# Sheet1.net
KiCad netlist of a schematic drawn in Altium Designer
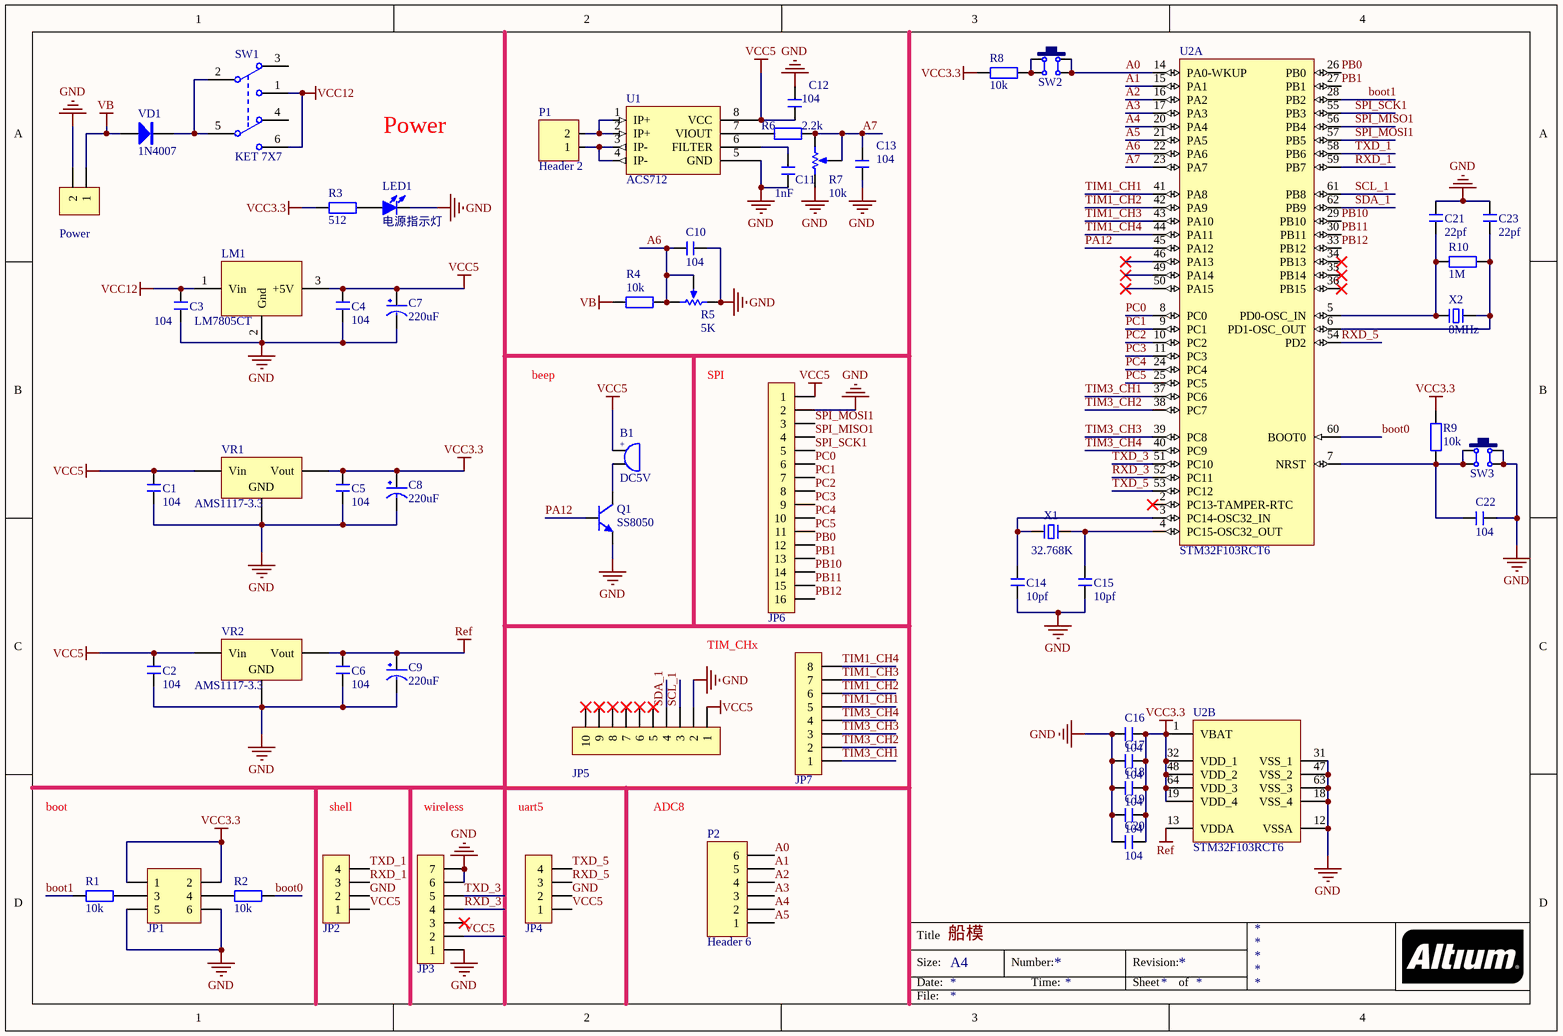
[diagram p0: Sheet1.SchDoc]

(export (version "E")
  (design (tool "Eeschema 10.0.6"))
  (components
    (comp (ref "B1")
      (value "DC5V")
      (footprint "蜂鸣器")
      (description "蜂鸣器")
      (fields (field (name "版权归属") "源创客"))
      (libsource (lib "未分类器件") (part "BEEP"))
    )
    (comp (ref "C1")
      (value "104")
      (footprint "0805")
      (description "无极性贴片电容")
      (fields (field (name "版权归属") "源创客"))
      (libsource (lib "电阻-电容-电感") (part "C"))
    )
    (comp (ref "C2")
      (value "104")
      (footprint "0805")
      (description "无极性贴片电容")
      (fields (field (name "版权归属") "源创客"))
      (libsource (lib "电阻-电容-电感") (part "C"))
    )
    (comp (ref "C3")
      (value "104")
      (footprint "0805")
      (description "无极性贴片电容")
      (fields (field (name "版权归属") "源创客"))
      (libsource (lib "电阻-电容-电感") (part "C"))
    )
    (comp (ref "C4")
      (value "104")
      (footprint "0805")
      (description "无极性贴片电容")
      (fields (field (name "版权归属") "源创客"))
      (libsource (lib "电阻-电容-电感") (part "C"))
    )
    (comp (ref "C5")
      (value "104")
      (footprint "0805")
      (description "无极性贴片电容")
      (fields (field (name "版权归属") "源创客"))
      (libsource (lib "电阻-电容-电感") (part "C"))
    )
    (comp (ref "C6")
      (value "104")
      (footprint "0805")
      (description "无极性贴片电容")
      (fields (field (name "版权归属") "源创客"))
      (libsource (lib "电阻-电容-电感") (part "C"))
    )
    (comp (ref "C7")
      (value "220uF")
      (footprint "CC6.56.5")
      (libsource (lib "WarShip V3 STM32103封装库") (part "CAP"))
    )
    (comp (ref "C8")
      (value "220uF")
      (footprint "CC6.56.5")
      (libsource (lib "WarShip V3 STM32103封装库") (part "CAP"))
    )
    (comp (ref "C9")
      (value "220uF")
      (footprint "CC6.56.5")
      (libsource (lib "WarShip V3 STM32103封装库") (part "CAP"))
    )
    (comp (ref "C10")
      (value "104")
      (footprint "0805")
      (description "无极性贴片电容")
      (fields (field (name "版权归属") "源创客"))
      (libsource (lib "电阻-电容-电感") (part "C"))
    )
    (comp (ref "C11")
      (value "1nF")
      (footprint "0805")
      (description "无极性贴片电容")
      (fields (field (name "版权归属") "源创客"))
      (libsource (lib "电阻-电容-电感") (part "C"))
    )
    (comp (ref "C12")
      (value "104")
      (footprint "0805")
      (description "无极性贴片电容")
      (fields (field (name "版权归属") "源创客"))
      (libsource (lib "电阻-电容-电感") (part "C"))
    )
    (comp (ref "C13")
      (value "104")
      (footprint "0805")
      (description "无极性贴片电容")
      (fields (field (name "版权归属") "源创客"))
      (libsource (lib "电阻-电容-电感") (part "C"))
    )
    (comp (ref "C14")
      (value "10pf")
      (footprint "0805")
      (description "无极性贴片电容")
      (fields (field (name "版权归属") "源创客"))
      (libsource (lib "电阻-电容-电感") (part "C"))
    )
    (comp (ref "C15")
      (value "10pf")
      (footprint "0805")
      (description "无极性贴片电容")
      (fields (field (name "版权归属") "源创客"))
      (libsource (lib "电阻-电容-电感") (part "C"))
    )
    (comp (ref "C16")
      (value "104")
      (footprint "0805")
      (description "无极性贴片电容")
      (fields (field (name "版权归属") "源创客"))
      (libsource (lib "电阻-电容-电感") (part "C"))
    )
    (comp (ref "C17")
      (value "104")
      (footprint "0805")
      (description "无极性贴片电容")
      (fields (field (name "版权归属") "源创客"))
      (libsource (lib "电阻-电容-电感") (part "C"))
    )
    (comp (ref "C18")
      (value "104")
      (footprint "0805")
      (description "无极性贴片电容")
      (fields (field (name "版权归属") "源创客"))
      (libsource (lib "电阻-电容-电感") (part "C"))
    )
    (comp (ref "C19")
      (value "104")
      (footprint "0805")
      (description "无极性贴片电容")
      (fields (field (name "版权归属") "源创客"))
      (libsource (lib "电阻-电容-电感") (part "C"))
    )
    (comp (ref "C20")
      (value "104")
      (footprint "0805")
      (description "无极性贴片电容")
      (fields (field (name "版权归属") "源创客"))
      (libsource (lib "电阻-电容-电感") (part "C"))
    )
    (comp (ref "C21")
      (value "22pf")
      (footprint "0805")
      (description "无极性贴片电容")
      (fields (field (name "版权归属") "源创客"))
      (libsource (lib "电阻-电容-电感") (part "C"))
    )
    (comp (ref "C22")
      (value "104")
      (footprint "0805")
      (description "无极性贴片电容")
      (fields (field (name "版权归属") "源创客"))
      (libsource (lib "电阻-电容-电感") (part "C"))
    )
    (comp (ref "C23")
      (value "22pf")
      (footprint "0805")
      (description "无极性贴片电容")
      (fields (field (name "版权归属") "源创客"))
      (libsource (lib "电阻-电容-电感") (part "C"))
    )
    (comp (ref "JP1")
      (value "Header3X2")
      (footprint "HDR2X3")
      (description "3*2P接插件")
      (fields (field (name "版权归属") "源创客"))
      (libsource (lib "接插件") (part "Header 3X2"))
    )
    (comp (ref "JP2")
      (value "HDR-1X4")
      (footprint "HDR1X4")
      (description "4P接插件")
      (fields (field (name "版权归属") "源创客"))
      (libsource (lib "接插件") (part "Header 4"))
    )
    (comp (ref "JP3")
      (value "HDR-1X7")
      (footprint "射频模块")
      (description "7P接插件")
      (fields (field (name "版权归属") "源创客"))
      (libsource (lib "接插件") (part "Header 7"))
    )
    (comp (ref "JP4")
      (value "HDR-1X4")
      (footprint "HDR1X4")
      (description "4P接插件")
      (fields (field (name "版权归属") "源创客"))
      (libsource (lib "接插件") (part "Header 4"))
    )
    (comp (ref "JP5")
      (value "HDR-1X10")
      (footprint "HDR1X10")
      (description "10P接插件")
      (fields (field (name "版权归属") "源创客"))
      (libsource (lib "接插件") (part "Header 10"))
    )
    (comp (ref "JP6")
      (value "HDR-1X16")
      (footprint "HDR1X16")
      (description "16P接插件")
      (fields (field (name "版权归属") "源创客"))
      (libsource (lib "接插件") (part "Header 16"))
    )
    (comp (ref "JP7")
      (value "HDR-1X8")
      (footprint "HDR1X10")
      (description "8P接插件")
      (fields (field (name "版权归属") "源创客"))
      (libsource (lib "接插件") (part "Header 8"))
    )
    (comp (ref "LED1")
      (value "电源指示灯")
      (footprint "5mmLED")
      (description "插件LED")
      (fields (field (name "版权归属") "源创客"))
      (libsource (lib "LED") (part "LED-3MM"))
    )
    (comp (ref "LM1")
      (value "LM7805CT")
      (footprint "TO254P1524X480-3N")
      (libsource (lib "MyInt_Lib") (part "LM7805CT"))
    )
    (comp (ref "P1")
      (value "Header 2")
      (footprint "2p 5.08")
      (description "Header, 2-Pin")
      (fields (field (name "PUBLISHER") "Altium Limited"))
      (libsource (lib "Miscellaneous Connectors") (part "Header 2"))
    )
    (comp (ref "P2")
      (value "Header 6")
      (footprint "HDR1X6")
      (description "Header, 6-Pin")
      (fields (field (name "PUBLISHER") "Altium Limited"))
      (libsource (lib "Miscellaneous Connectors") (part "Header 6"))
    )
    (comp (ref "Power")
      (value "HDR-1X2")
      (footprint "2p 5.08")
      (description "2P接插件")
      (fields (field (name "版权归属") "源创客"))
      (libsource (lib "接插件") (part "Header 2"))
    )
    (comp (ref "Q1")
      (value "SS8050")
      (footprint "小功率三极管")
      (description "高频放大-NPN型")
      (fields (field (name "版权归属") "源创客"))
      (libsource (lib "三极管") (part "8050-DIP"))
    )
    (comp (ref "R1")
      (value "10k")
      (footprint "0805")
      (description "贴片电阻")
      (fields (field (name "版权归属") "源创客"))
      (libsource (lib "电阻-电容-电感") (part "R"))
    )
    (comp (ref "R2")
      (value "10k")
      (footprint "0805")
      (description "贴片电阻")
      (fields (field (name "版权归属") "源创客"))
      (libsource (lib "电阻-电容-电感") (part "R"))
    )
    (comp (ref "R3")
      (value "512")
      (footprint "0805")
      (description "贴片电阻")
      (fields (field (name "版权归属") "源创客"))
      (libsource (lib "电阻-电容-电感") (part "R"))
    )
    (comp (ref "R4")
      (value "10k")
      (footprint "0805")
      (description "贴片电阻")
      (fields (field (name "版权归属") "源创客"))
      (libsource (lib "电阻-电容-电感") (part "R"))
    )
    (comp (ref "R5")
      (value "5K")
      (footprint "精密可调电位器")
      (description "Potentiometer")
      (fields (field (name "Comment") "RPot") (field (name "PUBLISHER") "Altium Limited"))
      (libsource (lib "Miscellaneous Devices") (part "RPot"))
    )
    (comp (ref "R6")
      (value "2.2k")
      (footprint "0805")
      (description "贴片电阻")
      (fields (field (name "版权归属") "源创客"))
      (libsource (lib "电阻-电容-电感") (part "R"))
    )
    (comp (ref "R7")
      (value "10k")
      (footprint "精密可调电位器")
      (description "Potentiometer")
      (fields (field (name "Comment") "RPot") (field (name "PUBLISHER") "Altium Limited"))
      (libsource (lib "Miscellaneous Devices") (part "RPot"))
    )
    (comp (ref "R8")
      (value "10k")
      (footprint "0805")
      (description "贴片电阻")
      (fields (field (name "版权归属") "源创客"))
      (libsource (lib "电阻-电容-电感") (part "R"))
    )
    (comp (ref "R9")
      (value "10k")
      (footprint "0805")
      (description "贴片电阻")
      (fields (field (name "版权归属") "源创客"))
      (libsource (lib "电阻-电容-电感") (part "R"))
    )
    (comp (ref "R10")
      (value "1M")
      (footprint "0805")
      (description "贴片电阻")
      (fields (field (name "版权归属") "源创客"))
      (libsource (lib "电阻-电容-电感") (part "R"))
    )
    (comp (ref "SW1")
      (value "KET 7X7")
      (footprint "BTN8.5*8.5")
      (description "7*7自锁开关")
      (fields (field (name "版权归属") "源创客"))
      (libsource (lib "按键-开关") (part "KET 7X7"))
    )
    (comp (ref "SW2")
      (value "6x6x5")
      (footprint "按钮")
      (description "直插6x6轻触开关")
      (fields (field (name "版权归属") "源创客"))
      (libsource (lib "按键-开关") (part "TSW DIP-6x6"))
    )
    (comp (ref "SW3")
      (value "6x6x5")
      (footprint "按钮")
      (description "直插6x6轻触开关")
      (fields (field (name "版权归属") "源创客"))
      (libsource (lib "按键-开关") (part "TSW DIP-6x6"))
    )
    (comp (ref "U1")
      (value "ACS712")
      (footprint "SOP8 - duplicate")
      (libsource (lib "Schlib1") (part "ACS712"))
    )
    (comp (ref "U2")
      (value "STM32F103RCT6")
      (footprint "STM-LQFP64_M")
      (libsource (lib "STMicroelectronics STM32 F1") (part "STM32F103RCT6"))
    )
    (comp (ref "VD1")
      (value "1N4007")
      (footprint "DIODE_SOP")
      (description "整流二极管")
      (fields (field (name "版权归属") "源创客"))
      (libsource (lib "二极管-整流桥") (part "1N4007"))
    )
    (comp (ref "VR1")
      (value "AMS1117-3.3")
      (footprint "SOT-223")
      (description "低压差线性稳压(LDO)")
      (libsource (lib "Miscellaneous Devices LC") (part "SOT-223 AMS1117-3.3"))
    )
    (comp (ref "VR2")
      (value "AMS1117-3.3")
      (footprint "SOT-223")
      (description "低压差线性稳压(LDO)")
      (libsource (lib "Miscellaneous Devices LC") (part "SOT-223 AMS1117-3.3"))
    )
    (comp (ref "X1")
      (value "32.768K")
      (footprint "CAPR5-4X5")
      (description "2脚晶振")
      (fields (field (name "版权归属") "源创客"))
      (libsource (lib "保险丝-晶振") (part "XTAL-2"))
    )
    (comp (ref "X2")
      (value "8MHz")
      (footprint "直插晶振")
      (description "2脚晶振")
      (fields (field (name "版权归属") "源创客"))
      (libsource (lib "保险丝-晶振") (part "XTAL-2"))
    )
  )
  (nets
    (net (code "1") (name "/A0") (class "Default")
      (node (ref "P2") (pin "6") (pinfunction "6_6") (pintype "passive"))
      (node (ref "SW2") (pin "2") (pinfunction "2_2") (pintype "passive"))
      (node (ref "SW2") (pin "3") (pinfunction "3_3") (pintype "passive"))
      (node (ref "U2") (pin "14") (pinfunction "PA0-WKUP_14") (pintype "bidirectional"))
    )
    (net (code "2") (name "/A1") (class "Default")
      (node (ref "P2") (pin "5") (pinfunction "5_5") (pintype "passive"))
      (node (ref "U2") (pin "15") (pinfunction "PA1_15") (pintype "bidirectional"))
    )
    (net (code "3") (name "/A2") (class "Default")
      (node (ref "P2") (pin "4") (pinfunction "4_4") (pintype "passive"))
      (node (ref "U2") (pin "16") (pinfunction "PA2_16") (pintype "bidirectional"))
    )
    (net (code "4") (name "/A3") (class "Default")
      (node (ref "P2") (pin "3") (pinfunction "3_3") (pintype "passive"))
      (node (ref "U2") (pin "17") (pinfunction "PA3_17") (pintype "bidirectional"))
    )
    (net (code "5") (name "/A4") (class "Default")
      (node (ref "P2") (pin "2") (pinfunction "2_2") (pintype "passive"))
      (node (ref "U2") (pin "20") (pinfunction "PA4_20") (pintype "bidirectional"))
    )
    (net (code "6") (name "/A5") (class "Default")
      (node (ref "P2") (pin "1") (pinfunction "1_1") (pintype "passive"))
      (node (ref "U2") (pin "21") (pinfunction "PA5_21") (pintype "bidirectional"))
    )
    (net (code "7") (name "/A6") (class "Default")
      (node (ref "C10") (pin "1") (pinfunction "1_1") (pintype "passive"))
      (node (ref "R4") (pin "2") (pinfunction "2_2") (pintype "passive"))
      (node (ref "R5") (pin "1") (pinfunction "BOT_1") (pintype "passive"))
      (node (ref "R5") (pin "2") (pinfunction "TAP_2") (pintype "passive"))
      (node (ref "U2") (pin "22") (pinfunction "PA6_22") (pintype "bidirectional"))
    )
    (net (code "8") (name "/A7") (class "Default")
      (node (ref "C13") (pin "1") (pinfunction "1_1") (pintype "passive"))
      (node (ref "R6") (pin "2") (pinfunction "2_2") (pintype "passive"))
      (node (ref "R7") (pin "1") (pinfunction "BOT_1") (pintype "passive"))
      (node (ref "R7") (pin "2") (pinfunction "TAP_2") (pintype "passive"))
      (node (ref "U2") (pin "23") (pinfunction "PA7_23") (pintype "bidirectional"))
    )
    (net (code "9") (name "/PA12") (class "Default")
      (node (ref "Q1") (pin "2") (pinfunction "B_2") (pintype "passive"))
      (node (ref "U2") (pin "45") (pinfunction "PA12_45") (pintype "bidirectional"))
    )
    (net (code "10") (name "/PB0") (class "Default")
      (node (ref "JP6") (pin "12") (pinfunction "12_12") (pintype "passive"))
      (node (ref "U2") (pin "26") (pinfunction "PB0_26") (pintype "bidirectional"))
    )
    (net (code "11") (name "/PB1") (class "Default")
      (node (ref "JP6") (pin "13") (pinfunction "13_13") (pintype "passive"))
      (node (ref "U2") (pin "27") (pinfunction "PB1_27") (pintype "bidirectional"))
    )
    (net (code "12") (name "/PB10") (class "Default")
      (node (ref "JP6") (pin "14") (pinfunction "14_14") (pintype "passive"))
      (node (ref "U2") (pin "29") (pinfunction "PB10_29") (pintype "bidirectional"))
    )
    (net (code "13") (name "/PB11") (class "Default")
      (node (ref "JP6") (pin "15") (pinfunction "15_15") (pintype "passive"))
      (node (ref "U2") (pin "30") (pinfunction "PB11_30") (pintype "bidirectional"))
    )
    (net (code "14") (name "/PB12") (class "Default")
      (node (ref "JP6") (pin "16") (pinfunction "16_16") (pintype "passive"))
      (node (ref "U2") (pin "33") (pinfunction "PB12_33") (pintype "bidirectional"))
    )
    (net (code "15") (name "/PC0") (class "Default")
      (node (ref "JP6") (pin "6") (pinfunction "6_6") (pintype "passive"))
      (node (ref "U2") (pin "8") (pinfunction "PC0_8") (pintype "bidirectional"))
    )
    (net (code "16") (name "/PC1") (class "Default")
      (node (ref "JP6") (pin "7") (pinfunction "7_7") (pintype "passive"))
      (node (ref "U2") (pin "9") (pinfunction "PC1_9") (pintype "bidirectional"))
    )
    (net (code "17") (name "/PC2") (class "Default")
      (node (ref "JP6") (pin "8") (pinfunction "8_8") (pintype "passive"))
      (node (ref "U2") (pin "10") (pinfunction "PC2_10") (pintype "bidirectional"))
    )
    (net (code "18") (name "/PC3") (class "Default")
      (node (ref "JP6") (pin "9") (pinfunction "9_9") (pintype "passive"))
      (node (ref "U2") (pin "11") (pinfunction "PC3_11") (pintype "bidirectional"))
    )
    (net (code "19") (name "/PC4") (class "Default")
      (node (ref "JP6") (pin "10") (pinfunction "10_10") (pintype "passive"))
      (node (ref "U2") (pin "24") (pinfunction "PC4_24") (pintype "bidirectional"))
    )
    (net (code "20") (name "/PC5") (class "Default")
      (node (ref "JP6") (pin "11") (pinfunction "11_11") (pintype "passive"))
      (node (ref "U2") (pin "25") (pinfunction "PC5_25") (pintype "bidirectional"))
    )
    (net (code "21") (name "/RXD_1") (class "Default")
      (node (ref "JP2") (pin "3") (pinfunction "3_3") (pintype "passive"))
      (node (ref "U2") (pin "59") (pinfunction "PB7_59") (pintype "bidirectional"))
    )
    (net (code "22") (name "/RXD_3") (class "Default")
      (node (ref "JP3") (pin "4") (pinfunction "4_4") (pintype "passive"))
      (node (ref "U2") (pin "52") (pinfunction "PC11_52") (pintype "bidirectional"))
    )
    (net (code "23") (name "/RXD_5") (class "Default")
      (node (ref "JP4") (pin "3") (pinfunction "3_3") (pintype "passive"))
      (node (ref "U2") (pin "54") (pinfunction "PD2_54") (pintype "bidirectional"))
    )
    (net (code "24") (name "/SCL_1") (class "Default")
      (node (ref "JP5") (pin "3") (pinfunction "3_3") (pintype "passive"))
      (node (ref "U2") (pin "61") (pinfunction "PB8_61") (pintype "bidirectional"))
    )
    (net (code "25") (name "/SDA_1") (class "Default")
      (node (ref "JP5") (pin "4") (pinfunction "4_4") (pintype "passive"))
      (node (ref "U2") (pin "62") (pinfunction "PB9_62") (pintype "bidirectional"))
    )
    (net (code "26") (name "/SPI_MISO1") (class "Default")
      (node (ref "JP6") (pin "4") (pinfunction "4_4") (pintype "passive"))
      (node (ref "U2") (pin "56") (pinfunction "PB4_56") (pintype "bidirectional"))
    )
    (net (code "27") (name "/SPI_MOSI1") (class "Default")
      (node (ref "JP6") (pin "3") (pinfunction "3_3") (pintype "passive"))
      (node (ref "U2") (pin "57") (pinfunction "PB5_57") (pintype "bidirectional"))
    )
    (net (code "28") (name "/SPI_SCK1") (class "Default")
      (node (ref "JP6") (pin "5") (pinfunction "5_5") (pintype "passive"))
      (node (ref "U2") (pin "55") (pinfunction "PB3_55") (pintype "bidirectional"))
    )
    (net (code "29") (name "/TIM1_CH1") (class "Default")
      (node (ref "JP7") (pin "5") (pinfunction "5_5") (pintype "passive"))
      (node (ref "U2") (pin "41") (pinfunction "PA8_41") (pintype "bidirectional"))
    )
    (net (code "30") (name "/TIM1_CH2") (class "Default")
      (node (ref "JP7") (pin "6") (pinfunction "6_6") (pintype "passive"))
      (node (ref "U2") (pin "42") (pinfunction "PA9_42") (pintype "bidirectional"))
    )
    (net (code "31") (name "/TIM1_CH3") (class "Default")
      (node (ref "JP7") (pin "7") (pinfunction "7_7") (pintype "passive"))
      (node (ref "U2") (pin "43") (pinfunction "PA10_43") (pintype "bidirectional"))
    )
    (net (code "32") (name "/TIM1_CH4") (class "Default")
      (node (ref "JP7") (pin "8") (pinfunction "8_8") (pintype "passive"))
      (node (ref "U2") (pin "44") (pinfunction "PA11_44") (pintype "bidirectional"))
    )
    (net (code "33") (name "/TIM3_CH1") (class "Default")
      (node (ref "JP7") (pin "1") (pinfunction "1_1") (pintype "passive"))
      (node (ref "U2") (pin "37") (pinfunction "PC6_37") (pintype "bidirectional"))
    )
    (net (code "34") (name "/TIM3_CH2") (class "Default")
      (node (ref "JP7") (pin "2") (pinfunction "2_2") (pintype "passive"))
      (node (ref "U2") (pin "38") (pinfunction "PC7_38") (pintype "bidirectional"))
    )
    (net (code "35") (name "/TIM3_CH3") (class "Default")
      (node (ref "JP7") (pin "3") (pinfunction "3_3") (pintype "passive"))
      (node (ref "U2") (pin "39") (pinfunction "PC8_39") (pintype "bidirectional"))
    )
    (net (code "36") (name "/TIM3_CH4") (class "Default")
      (node (ref "JP7") (pin "4") (pinfunction "4_4") (pintype "passive"))
      (node (ref "U2") (pin "40") (pinfunction "PC9_40") (pintype "bidirectional"))
    )
    (net (code "37") (name "/TXD_1") (class "Default")
      (node (ref "JP2") (pin "4") (pinfunction "4_4") (pintype "passive"))
      (node (ref "U2") (pin "58") (pinfunction "PB6_58") (pintype "bidirectional"))
    )
    (net (code "38") (name "/TXD_3") (class "Default")
      (node (ref "JP3") (pin "5") (pinfunction "5_5") (pintype "passive"))
      (node (ref "U2") (pin "51") (pinfunction "PC10_51") (pintype "bidirectional"))
    )
    (net (code "39") (name "/TXD_5") (class "Default")
      (node (ref "JP4") (pin "4") (pinfunction "4_4") (pintype "passive"))
      (node (ref "U2") (pin "53") (pinfunction "PC12_53") (pintype "bidirectional"))
    )
    (net (code "40") (name "/boot0") (class "Default")
      (node (ref "R2") (pin "1") (pinfunction "1_1") (pintype "passive"))
      (node (ref "U2") (pin "60") (pinfunction "BOOT0_60") (pintype "input"))
    )
    (net (code "41") (name "/boot1") (class "Default")
      (node (ref "R1") (pin "1") (pinfunction "1_1") (pintype "passive"))
      (node (ref "U2") (pin "28") (pinfunction "PB2_28") (pintype "bidirectional"))
    )
    (net (code "42") (name "GND") (class "Default")
      (node (ref "C1") (pin "2") (pinfunction "2_2") (pintype "passive"))
      (node (ref "C10") (pin "2") (pinfunction "2_2") (pintype "passive"))
      (node (ref "C11") (pin "2") (pinfunction "2_2") (pintype "passive"))
      (node (ref "C12") (pin "1") (pinfunction "1_1") (pintype "passive"))
      (node (ref "C13") (pin "2") (pinfunction "2_2") (pintype "passive"))
      (node (ref "C14") (pin "1") (pinfunction "1_1") (pintype "passive"))
      (node (ref "C15") (pin "1") (pinfunction "1_1") (pintype "passive"))
      (node (ref "C16") (pin "1") (pinfunction "1_1") (pintype "passive"))
      (node (ref "C17") (pin "1") (pinfunction "1_1") (pintype "passive"))
      (node (ref "C18") (pin "1") (pinfunction "1_1") (pintype "passive"))
      (node (ref "C19") (pin "1") (pinfunction "1_1") (pintype "passive"))
      (node (ref "C2") (pin "2") (pinfunction "2_2") (pintype "passive"))
      (node (ref "C20") (pin "1") (pinfunction "1_1") (pintype "passive"))
      (node (ref "C21") (pin "2") (pinfunction "2_2") (pintype "passive"))
      (node (ref "C22") (pin "2") (pinfunction "2_2") (pintype "passive"))
      (node (ref "C23") (pin "2") (pinfunction "2_2") (pintype "passive"))
      (node (ref "C3") (pin "2") (pinfunction "2_2") (pintype "passive"))
      (node (ref "C4") (pin "2") (pinfunction "2_2") (pintype "passive"))
      (node (ref "C5") (pin "2") (pinfunction "2_2") (pintype "passive"))
      (node (ref "C6") (pin "2") (pinfunction "2_2") (pintype "passive"))
      (node (ref "C7") (pin "2") (pinfunction "GND_2") (pintype "passive"))
      (node (ref "C8") (pin "2") (pinfunction "GND_2") (pintype "passive"))
      (node (ref "C9") (pin "2") (pinfunction "GND_2") (pintype "passive"))
      (node (ref "JP1") (pin "5") (pinfunction "5_5") (pintype "passive"))
      (node (ref "JP1") (pin "6") (pinfunction "6_6") (pintype "passive"))
      (node (ref "JP2") (pin "2") (pinfunction "2_2") (pintype "passive"))
      (node (ref "JP3") (pin "1") (pinfunction "1_1") (pintype "passive"))
      (node (ref "JP3") (pin "6") (pinfunction "6_6") (pintype "passive"))
      (node (ref "JP3") (pin "7") (pinfunction "7_7") (pintype "passive"))
      (node (ref "JP4") (pin "2") (pinfunction "2_2") (pintype "passive"))
      (node (ref "JP5") (pin "2") (pinfunction "2_2") (pintype "passive"))
      (node (ref "JP6") (pin "2") (pinfunction "2_2") (pintype "passive"))
      (node (ref "LED1") (pin "2") (pinfunction "K_2") (pintype "passive"))
      (node (ref "LM1") (pin "2") (pinfunction "Gnd_2") (pintype "passive"))
      (node (ref "Power") (pin "2") (pinfunction "2_2") (pintype "passive"))
      (node (ref "Q1") (pin "1") (pinfunction "E_1") (pintype "passive"))
      (node (ref "R5") (pin "3") (pinfunction "TOP_3") (pintype "passive"))
      (node (ref "R7") (pin "3") (pinfunction "TOP_3") (pintype "passive"))
      (node (ref "SW3") (pin "2") (pinfunction "2_2") (pintype "passive"))
      (node (ref "SW3") (pin "3") (pinfunction "3_3") (pintype "passive"))
      (node (ref "U1") (pin "5") (pinfunction "GND_5") (pintype "power_in"))
      (node (ref "U2") (pin "12") (pinfunction "VSSA_12") (pintype "power_in"))
      (node (ref "U2") (pin "18") (pinfunction "VSS_4_18") (pintype "power_in"))
      (node (ref "U2") (pin "31") (pinfunction "VSS_1_31") (pintype "power_in"))
      (node (ref "U2") (pin "47") (pinfunction "VSS_2_47") (pintype "power_in"))
      (node (ref "U2") (pin "63") (pinfunction "VSS_3_63") (pintype "power_in"))
      (node (ref "VR1") (pin "1") (pinfunction "GND_1") (pintype "passive"))
      (node (ref "VR2") (pin "1") (pinfunction "GND_1") (pintype "passive"))
    )
    (net (code "43") (name "Net-(JP1-Pad3)") (class "Default")
      (node (ref "JP1") (pin "3") (pinfunction "3_3") (pintype "passive"))
      (node (ref "R1") (pin "2") (pinfunction "2_2") (pintype "passive"))
    )
    (net (code "44") (name "Net-(JP1-Pad4)") (class "Default")
      (node (ref "JP1") (pin "4") (pinfunction "4_4") (pintype "passive"))
      (node (ref "R2") (pin "2") (pinfunction "2_2") (pintype "passive"))
    )
    (net (code "45") (name "Net-(LED1-A)") (class "Default")
      (node (ref "LED1") (pin "1") (pinfunction "A_1") (pintype "passive"))
      (node (ref "R3") (pin "2") (pinfunction "2_2") (pintype "passive"))
    )
    (net (code "46") (name "Net-(P1-Pad1)") (class "Default")
      (node (ref "P1") (pin "1") (pinfunction "1_1") (pintype "passive"))
      (node (ref "U1") (pin "3") (pinfunction "IP-_3") (pintype "output"))
      (node (ref "U1") (pin "4") (pinfunction "IP-_4") (pintype "output"))
    )
    (net (code "47") (name "Net-(P1-Pad2)") (class "Default")
      (node (ref "P1") (pin "2") (pinfunction "2_2") (pintype "passive"))
      (node (ref "U1") (pin "1") (pinfunction "IP+_1") (pintype "input"))
      (node (ref "U1") (pin "2") (pinfunction "IP+_2") (pintype "input"))
    )
    (net (code "48") (name "Net-(Q1-C)") (class "Default")
      (node (ref "B1") (pin "2") (pinfunction "2_2") (pintype "passive"))
      (node (ref "Q1") (pin "3") (pinfunction "C_3") (pintype "passive"))
    )
    (net (code "49") (name "Net-(R8-Pad2)") (class "Default")
      (node (ref "R8") (pin "2") (pinfunction "2_2") (pintype "passive"))
      (node (ref "SW2") (pin "1") (pinfunction "1_1") (pintype "passive"))
      (node (ref "SW2") (pin "4") (pinfunction "4_4") (pintype "passive"))
    )
    (net (code "50") (name "Net-(U1-FILTER)") (class "Default")
      (node (ref "C11") (pin "1") (pinfunction "1_1") (pintype "passive"))
      (node (ref "U1") (pin "6") (pinfunction "FILTER_6") (pintype "power_in"))
    )
    (net (code "51") (name "Net-(U1-VIOUT)") (class "Default")
      (node (ref "R6") (pin "1") (pinfunction "1_1") (pintype "passive"))
      (node (ref "U1") (pin "7") (pinfunction "VIOUT_7") (pintype "power_in"))
    )
    (net (code "52") (name "Net-(U2A-NRST)") (class "Default")
      (node (ref "C22") (pin "1") (pinfunction "1_1") (pintype "passive"))
      (node (ref "R9") (pin "1") (pinfunction "1_1") (pintype "passive"))
      (node (ref "SW3") (pin "1") (pinfunction "1_1") (pintype "passive"))
      (node (ref "SW3") (pin "4") (pinfunction "4_4") (pintype "passive"))
      (node (ref "U2") (pin "7") (pinfunction "NRST_7") (pintype "bidirectional"))
    )
    (net (code "53") (name "Net-(U2A-PC14-OSC32_IN)") (class "Default")
      (node (ref "C14") (pin "2") (pinfunction "2_2") (pintype "passive"))
      (node (ref "U2") (pin "3") (pinfunction "PC14-OSC32_IN_3") (pintype "bidirectional"))
      (node (ref "X1") (pin "1") (pinfunction "1_1") (pintype "passive"))
    )
    (net (code "54") (name "Net-(U2A-PC15-OSC32_OUT)") (class "Default")
      (node (ref "C15") (pin "2") (pinfunction "2_2") (pintype "passive"))
      (node (ref "U2") (pin "4") (pinfunction "PC15-OSC32_OUT_4") (pintype "bidirectional"))
      (node (ref "X1") (pin "2") (pinfunction "2_2") (pintype "passive"))
    )
    (net (code "55") (name "Net-(U2A-PD0-OSC_IN)") (class "Default")
      (node (ref "C21") (pin "1") (pinfunction "1_1") (pintype "passive"))
      (node (ref "R10") (pin "1") (pinfunction "1_1") (pintype "passive"))
      (node (ref "U2") (pin "5") (pinfunction "PD0-OSC_IN_5") (pintype "bidirectional"))
      (node (ref "X2") (pin "1") (pinfunction "1_1") (pintype "passive"))
    )
    (net (code "56") (name "Net-(U2A-PD1-OSC_OUT)") (class "Default")
      (node (ref "C23") (pin "1") (pinfunction "1_1") (pintype "passive"))
      (node (ref "R10") (pin "2") (pinfunction "2_2") (pintype "passive"))
      (node (ref "U2") (pin "6") (pinfunction "PD1-OSC_OUT_6") (pintype "bidirectional"))
      (node (ref "X2") (pin "2") (pinfunction "2_2") (pintype "passive"))
    )
    (net (code "57") (name "Net-(VD1-K)") (class "Default")
      (node (ref "SW1") (pin "2") (pinfunction "COM2_2") (pintype "passive"))
      (node (ref "SW1") (pin "5") (pinfunction "COM2_5") (pintype "passive"))
      (node (ref "VD1") (pin "2") (pinfunction "K_2") (pintype "passive"))
    )
    (net (code "58") (name "Ref") (class "Default")
      (node (ref "C6") (pin "1") (pinfunction "1_1") (pintype "passive"))
      (node (ref "C9") (pin "1") (pinfunction "VCC_1") (pintype "passive"))
      (node (ref "U2") (pin "13") (pinfunction "VDDA_13") (pintype "power_in"))
      (node (ref "VR2") (pin "2") (pinfunction "Vout_2") (pintype "passive"))
    )
    (net (code "59") (name "VB") (class "Default")
      (node (ref "Power") (pin "1") (pinfunction "1_1") (pintype "passive"))
      (node (ref "R4") (pin "1") (pinfunction "1_1") (pintype "passive"))
      (node (ref "VD1") (pin "1") (pinfunction "A_1") (pintype "passive"))
    )
    (net (code "60") (name "VCC3.3") (class "Default")
      (node (ref "C16") (pin "2") (pinfunction "2_2") (pintype "passive"))
      (node (ref "C17") (pin "2") (pinfunction "2_2") (pintype "passive"))
      (node (ref "C18") (pin "2") (pinfunction "2_2") (pintype "passive"))
      (node (ref "C19") (pin "2") (pinfunction "2_2") (pintype "passive"))
      (node (ref "C20") (pin "2") (pinfunction "2_2") (pintype "passive"))
      (node (ref "C5") (pin "1") (pinfunction "1_1") (pintype "passive"))
      (node (ref "C8") (pin "1") (pinfunction "VCC_1") (pintype "passive"))
      (node (ref "JP1") (pin "1") (pinfunction "1_1") (pintype "passive"))
      (node (ref "JP1") (pin "2") (pinfunction "2_2") (pintype "passive"))
      (node (ref "R3") (pin "1") (pinfunction "1_1") (pintype "passive"))
      (node (ref "R8") (pin "1") (pinfunction "1_1") (pintype "passive"))
      (node (ref "R9") (pin "2") (pinfunction "2_2") (pintype "passive"))
      (node (ref "U2") (pin "1") (pinfunction "VBAT_1") (pintype "power_in"))
      (node (ref "U2") (pin "19") (pinfunction "VDD_4_19") (pintype "power_in"))
      (node (ref "U2") (pin "32") (pinfunction "VDD_1_32") (pintype "power_in"))
      (node (ref "U2") (pin "48") (pinfunction "VDD_2_48") (pintype "power_in"))
      (node (ref "U2") (pin "64") (pinfunction "VDD_3_64") (pintype "power_in"))
      (node (ref "VR1") (pin "2") (pinfunction "Vout_2") (pintype "passive"))
    )
    (net (code "61") (name "VCC5") (class "Default")
      (node (ref "B1") (pin "1") (pinfunction "1_1") (pintype "passive"))
      (node (ref "C1") (pin "1") (pinfunction "1_1") (pintype "passive"))
      (node (ref "C12") (pin "2") (pinfunction "2_2") (pintype "passive"))
      (node (ref "C2") (pin "1") (pinfunction "1_1") (pintype "passive"))
      (node (ref "C4") (pin "1") (pinfunction "1_1") (pintype "passive"))
      (node (ref "C7") (pin "1") (pinfunction "VCC_1") (pintype "passive"))
      (node (ref "JP2") (pin "1") (pinfunction "1_1") (pintype "passive"))
      (node (ref "JP3") (pin "2") (pinfunction "2_2") (pintype "passive"))
      (node (ref "JP4") (pin "1") (pinfunction "1_1") (pintype "passive"))
      (node (ref "JP5") (pin "1") (pinfunction "1_1") (pintype "passive"))
      (node (ref "JP6") (pin "1") (pinfunction "1_1") (pintype "passive"))
      (node (ref "LM1") (pin "3") (pinfunction "+5V_3") (pintype "passive"))
      (node (ref "U1") (pin "8") (pinfunction "VCC_8") (pintype "power_in"))
      (node (ref "VR1") (pin "3") (pinfunction "Vin_3") (pintype "passive"))
      (node (ref "VR2") (pin "3") (pinfunction "Vin_3") (pintype "passive"))
    )
    (net (code "62") (name "VCC12") (class "Default")
      (node (ref "C3") (pin "1") (pinfunction "1_1") (pintype "passive"))
      (node (ref "LM1") (pin "1") (pinfunction "Vin_1") (pintype "passive"))
      (node (ref "SW1") (pin "1") (pinfunction "NC1_1") (pintype "passive"))
      (node (ref "SW1") (pin "6") (pinfunction "NC2_6") (pintype "passive"))
    )
    (net (code "63") (name "unconnected-(JP3-Pad3)") (class "Default")
      (node (ref "JP3") (pin "3") (pinfunction "3_3") (pintype "passive+no_connect"))
    )
    (net (code "64") (name "unconnected-(JP5-Pad5)") (class "Default")
      (node (ref "JP5") (pin "5") (pinfunction "5_5") (pintype "passive+no_connect"))
    )
    (net (code "65") (name "unconnected-(JP5-Pad6)") (class "Default")
      (node (ref "JP5") (pin "6") (pinfunction "6_6") (pintype "passive+no_connect"))
    )
    (net (code "66") (name "unconnected-(JP5-Pad7)") (class "Default")
      (node (ref "JP5") (pin "7") (pinfunction "7_7") (pintype "passive+no_connect"))
    )
    (net (code "67") (name "unconnected-(JP5-Pad8)") (class "Default")
      (node (ref "JP5") (pin "8") (pinfunction "8_8") (pintype "passive+no_connect"))
    )
    (net (code "68") (name "unconnected-(JP5-Pad9)") (class "Default")
      (node (ref "JP5") (pin "9") (pinfunction "9_9") (pintype "passive+no_connect"))
    )
    (net (code "69") (name "unconnected-(JP5-Pad10)") (class "Default")
      (node (ref "JP5") (pin "10") (pinfunction "10_10") (pintype "passive+no_connect"))
    )
    (net (code "70") (name "unconnected-(SW1-NO1-Pad3)") (class "Default")
      (node (ref "SW1") (pin "3") (pinfunction "NO1_3") (pintype "passive"))
    )
    (net (code "71") (name "unconnected-(SW1-NO2-Pad4)") (class "Default")
      (node (ref "SW1") (pin "4") (pinfunction "NO2_4") (pintype "passive"))
    )
    (net (code "72") (name "unconnected-(U2A-PA13-Pad46)") (class "Default")
      (node (ref "U2") (pin "46") (pinfunction "PA13_46") (pintype "bidirectional+no_connect"))
    )
    (net (code "73") (name "unconnected-(U2A-PA14-Pad49)") (class "Default")
      (node (ref "U2") (pin "49") (pinfunction "PA14_49") (pintype "bidirectional+no_connect"))
    )
    (net (code "74") (name "unconnected-(U2A-PA15-Pad50)") (class "Default")
      (node (ref "U2") (pin "50") (pinfunction "PA15_50") (pintype "bidirectional+no_connect"))
    )
    (net (code "75") (name "unconnected-(U2A-PB13-Pad34)") (class "Default")
      (node (ref "U2") (pin "34") (pinfunction "PB13_34") (pintype "bidirectional+no_connect"))
    )
    (net (code "76") (name "unconnected-(U2A-PB14-Pad35)") (class "Default")
      (node (ref "U2") (pin "35") (pinfunction "PB14_35") (pintype "bidirectional+no_connect"))
    )
    (net (code "77") (name "unconnected-(U2A-PB15-Pad36)") (class "Default")
      (node (ref "U2") (pin "36") (pinfunction "PB15_36") (pintype "bidirectional+no_connect"))
    )
    (net (code "78") (name "unconnected-(U2A-PC13-TAMPER-RTC-Pad2)") (class "Default")
      (node (ref "U2") (pin "2") (pinfunction "PC13-TAMPER-RTC_2") (pintype "bidirectional+no_connect"))
    )
  )
)
